# SCH_simple_bracelet_2025-11-06.net
KiCad netlist of a schematic drawn in EasyEDA
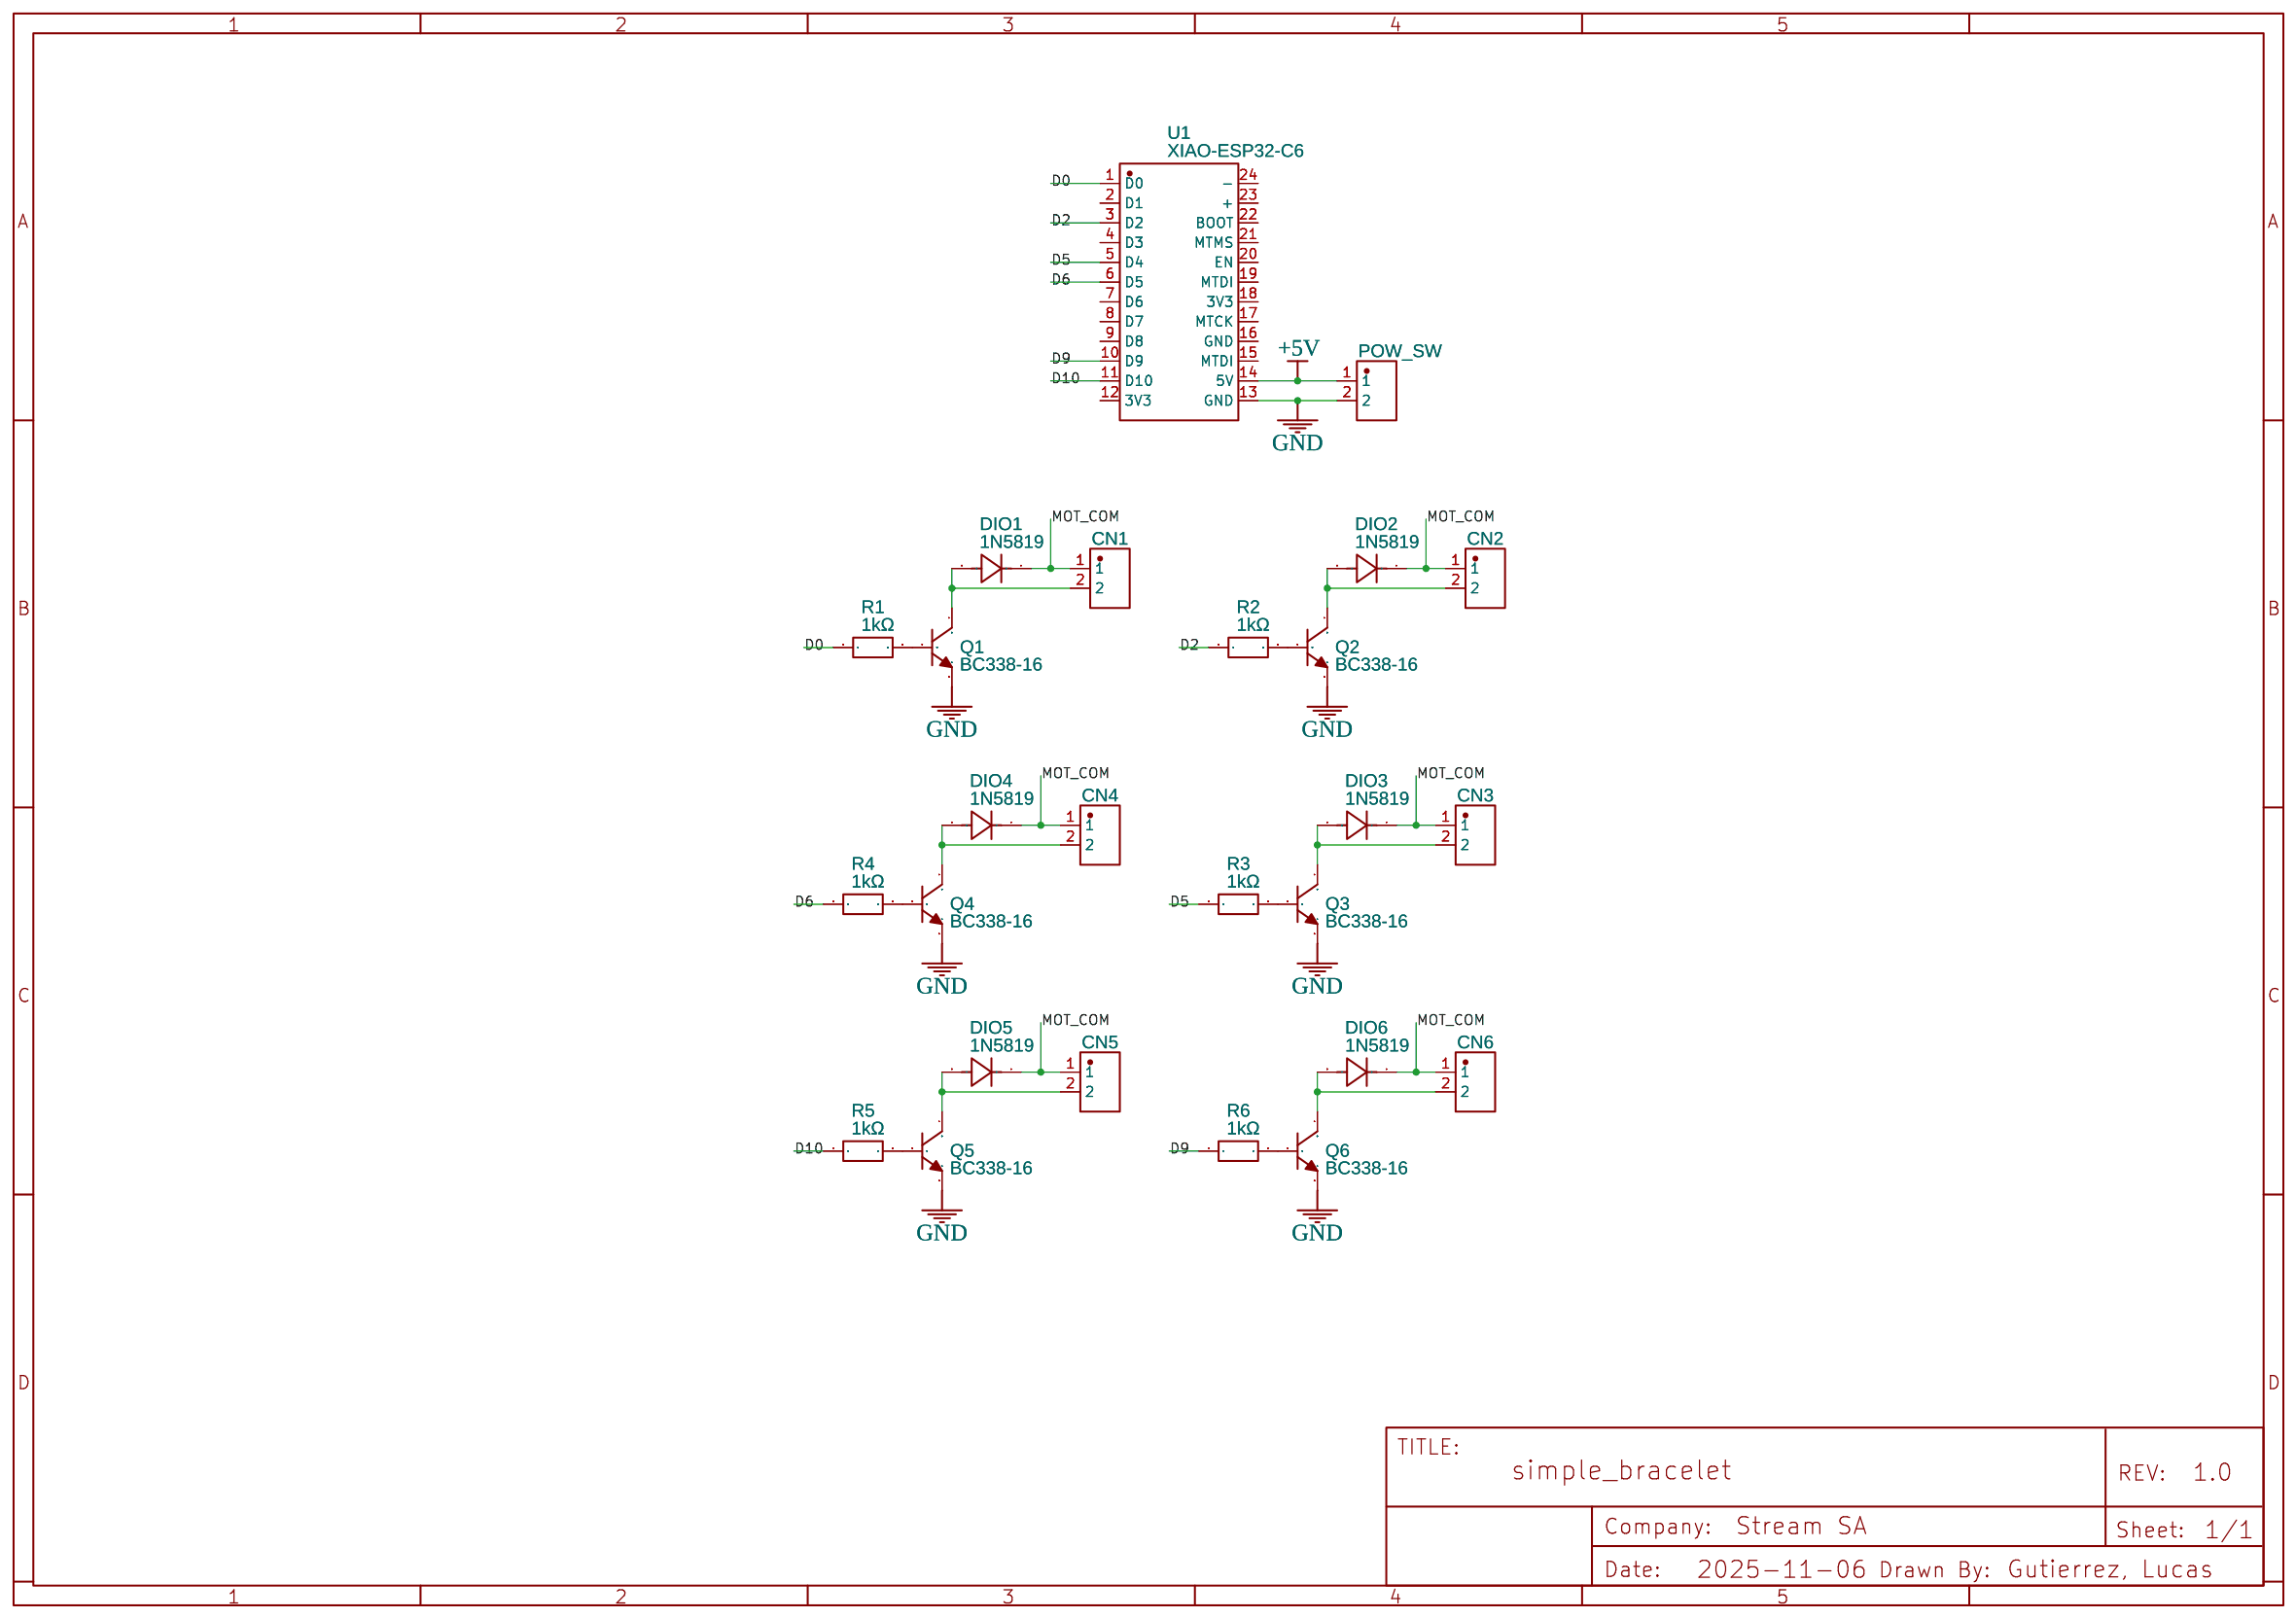
[diagram p0: schematic sheet]

(export (version "E")
  (design (tool "Eeschema 10.0.6"))
  (components
    (comp (ref "CN1")
      (value "2.54-2P WZDK-R PITCH CONNECTOR")
      (fields
        (field (name "Manufacturer Part") "2.54-2P WZDK-R Pitch Connector")
        (field (name "Manufacturer") "SHOU HAN(首韩)")
      )
      (libsource (lib "") (part "2.54-2P WZDK-R PITCH CONNECTOR_1"))
    )
    (comp (ref "CN2")
      (value "2.54-2P WZDK-R PITCH CONNECTOR")
      (fields
        (field (name "Manufacturer Part") "2.54-2P WZDK-R Pitch Connector")
        (field (name "Manufacturer") "SHOU HAN(首韩)")
      )
      (libsource (lib "") (part "2.54-2P WZDK-R PITCH CONNECTOR_1"))
    )
    (comp (ref "CN3")
      (value "2.54-2P WZDK-R PITCH CONNECTOR")
      (fields
        (field (name "Manufacturer Part") "2.54-2P WZDK-R Pitch Connector")
        (field (name "Manufacturer") "SHOU HAN(首韩)")
      )
      (libsource (lib "") (part "2.54-2P WZDK-R PITCH CONNECTOR_1"))
    )
    (comp (ref "CN4")
      (value "2.54-2P WZDK-R PITCH CONNECTOR")
      (fields
        (field (name "Manufacturer Part") "2.54-2P WZDK-R Pitch Connector")
        (field (name "Manufacturer") "SHOU HAN(首韩)")
      )
      (libsource (lib "") (part "2.54-2P WZDK-R PITCH CONNECTOR_1"))
    )
    (comp (ref "CN5")
      (value "2.54-2P WZDK-R PITCH CONNECTOR")
      (fields
        (field (name "Manufacturer Part") "2.54-2P WZDK-R Pitch Connector")
        (field (name "Manufacturer") "SHOU HAN(首韩)")
      )
      (libsource (lib "") (part "2.54-2P WZDK-R PITCH CONNECTOR_1"))
    )
    (comp (ref "CN6")
      (value "2.54-2P WZDK-R PITCH CONNECTOR")
      (fields
        (field (name "Manufacturer Part") "2.54-2P WZDK-R Pitch Connector")
        (field (name "Manufacturer") "SHOU HAN(首韩)")
      )
      (libsource (lib "") (part "2.54-2P WZDK-R PITCH CONNECTOR_1"))
    )
    (comp (ref "DIO1")
      (value "1N5819")
      (fields (field (name "Manufacturer Part") "1N5819散装0658") (field (name "Manufacturer") "YFW(佑风微)"))
      (libsource (lib "") (part "1N5819散装0658"))
    )
    (comp (ref "DIO2")
      (value "1N5819")
      (fields (field (name "Manufacturer Part") "1N5819散装0658") (field (name "Manufacturer") "YFW(佑风微)"))
      (libsource (lib "") (part "1N5819散装0658"))
    )
    (comp (ref "DIO3")
      (value "1N5819")
      (fields (field (name "Manufacturer Part") "1N5819散装0658") (field (name "Manufacturer") "YFW(佑风微)"))
      (libsource (lib "") (part "1N5819散装0658"))
    )
    (comp (ref "DIO4")
      (value "1N5819")
      (fields (field (name "Manufacturer Part") "1N5819散装0658") (field (name "Manufacturer") "YFW(佑风微)"))
      (libsource (lib "") (part "1N5819散装0658"))
    )
    (comp (ref "DIO5")
      (value "1N5819")
      (fields (field (name "Manufacturer Part") "1N5819散装0658") (field (name "Manufacturer") "YFW(佑风微)"))
      (libsource (lib "") (part "1N5819散装0658"))
    )
    (comp (ref "DIO6")
      (value "1N5819")
      (fields (field (name "Manufacturer Part") "1N5819散装0658") (field (name "Manufacturer") "YFW(佑风微)"))
      (libsource (lib "") (part "1N5819散装0658"))
    )
    (comp (ref "POW_SW")
      (value "2.54-2P WZDK-R PITCH CONNECTOR")
      (fields
        (field (name "Manufacturer Part") "2.54-2P WZDK-R Pitch Connector")
        (field (name "Manufacturer") "SHOU HAN(首韩)")
      )
      (libsource (lib "") (part "2.54-2P WZDK-R PITCH CONNECTOR"))
    )
    (comp (ref "Q1")
      (value "BC338-16")
      (fields (field (name "Manufacturer") "LGE(鲁光)"))
      (libsource (lib "") (part "BC338-16"))
    )
    (comp (ref "Q2")
      (value "BC338-16")
      (fields (field (name "Manufacturer") "LGE(鲁光)"))
      (libsource (lib "") (part "BC338-16"))
    )
    (comp (ref "Q3")
      (value "BC338-16")
      (fields (field (name "Manufacturer") "LGE(鲁光)"))
      (libsource (lib "") (part "BC338-16"))
    )
    (comp (ref "Q4")
      (value "BC338-16")
      (fields (field (name "Manufacturer") "LGE(鲁光)"))
      (libsource (lib "") (part "BC338-16"))
    )
    (comp (ref "Q5")
      (value "BC338-16")
      (fields (field (name "Manufacturer") "LGE(鲁光)"))
      (libsource (lib "") (part "BC338-16"))
    )
    (comp (ref "Q6")
      (value "BC338-16")
      (fields (field (name "Manufacturer") "LGE(鲁光)"))
      (libsource (lib "") (part "BC338-16"))
    )
    (comp (ref "R1")
      (value "1kΩ")
      (fields
        (field (name "Manufacturer Part") "CERAMIC RESISTOR 10W/ 2,2 OHM")
        (field (name "Manufacturer") "Visaton")
      )
      (libsource (lib "") (part "CERAMIC RESISTOR 10W/ 2,2 OHM"))
    )
    (comp (ref "R2")
      (value "1kΩ")
      (fields
        (field (name "Manufacturer Part") "CERAMIC RESISTOR 10W/ 2,2 OHM")
        (field (name "Manufacturer") "Visaton")
      )
      (libsource (lib "") (part "CERAMIC RESISTOR 10W/ 2,2 OHM"))
    )
    (comp (ref "R3")
      (value "1kΩ")
      (fields
        (field (name "Manufacturer Part") "CERAMIC RESISTOR 10W/ 2,2 OHM")
        (field (name "Manufacturer") "Visaton")
      )
      (libsource (lib "") (part "CERAMIC RESISTOR 10W/ 2,2 OHM"))
    )
    (comp (ref "R4")
      (value "1kΩ")
      (fields
        (field (name "Manufacturer Part") "CERAMIC RESISTOR 10W/ 2,2 OHM")
        (field (name "Manufacturer") "Visaton")
      )
      (libsource (lib "") (part "CERAMIC RESISTOR 10W/ 2,2 OHM"))
    )
    (comp (ref "R5")
      (value "1kΩ")
      (fields
        (field (name "Manufacturer Part") "CERAMIC RESISTOR 10W/ 2,2 OHM")
        (field (name "Manufacturer") "Visaton")
      )
      (libsource (lib "") (part "CERAMIC RESISTOR 10W/ 2,2 OHM"))
    )
    (comp (ref "R6")
      (value "1kΩ")
      (fields
        (field (name "Manufacturer Part") "CERAMIC RESISTOR 10W/ 2,2 OHM")
        (field (name "Manufacturer") "Visaton")
      )
      (libsource (lib "") (part "CERAMIC RESISTOR 10W/ 2,2 OHM"))
    )
    (comp (ref "U1") (value "XIAO-ESP32-C6") (libsource (lib "") (part "XIAO-ESP32-C6")))
  )
  (nets
    (net (code "1") (name "+5V") (class "Default")
      (node (ref "POW_SW") (pin "1") (pinfunction "1_1") (pintype "unspecified"))
      (node (ref "U1") (pin "14") (pinfunction "5V_14") (pintype "unspecified"))
    )
    (net (code "2") (name "/D0") (class "Default")
      (node (ref "R1") (pin "1") (pinfunction "1_1") (pintype "unspecified"))
      (node (ref "U1") (pin "1") (pinfunction "D0_1") (pintype "unspecified"))
    )
    (net (code "3") (name "/D2") (class "Default")
      (node (ref "R2") (pin "1") (pinfunction "1_1") (pintype "unspecified"))
      (node (ref "U1") (pin "3") (pinfunction "D2_3") (pintype "unspecified"))
    )
    (net (code "4") (name "/D5") (class "Default")
      (node (ref "R3") (pin "1") (pinfunction "1_1") (pintype "unspecified"))
      (node (ref "U1") (pin "5") (pinfunction "D4_5") (pintype "unspecified"))
    )
    (net (code "5") (name "/D6") (class "Default")
      (node (ref "R4") (pin "1") (pinfunction "1_1") (pintype "unspecified"))
      (node (ref "U1") (pin "6") (pinfunction "D5_6") (pintype "unspecified"))
    )
    (net (code "6") (name "/D9") (class "Default")
      (node (ref "R6") (pin "1") (pinfunction "1_1") (pintype "unspecified"))
      (node (ref "U1") (pin "10") (pinfunction "D9_10") (pintype "unspecified"))
    )
    (net (code "7") (name "/D10") (class "Default")
      (node (ref "R5") (pin "1") (pinfunction "1_1") (pintype "unspecified"))
      (node (ref "U1") (pin "11") (pinfunction "D10_11") (pintype "unspecified"))
    )
    (net (code "8") (name "/MOT_COM") (class "Default")
      (node (ref "CN1") (pin "1") (pinfunction "1_1") (pintype "unspecified"))
      (node (ref "CN2") (pin "1") (pinfunction "1_1") (pintype "unspecified"))
      (node (ref "CN3") (pin "1") (pinfunction "1_1") (pintype "unspecified"))
      (node (ref "CN4") (pin "1") (pinfunction "1_1") (pintype "unspecified"))
      (node (ref "CN5") (pin "1") (pinfunction "1_1") (pintype "unspecified"))
      (node (ref "CN6") (pin "1") (pinfunction "1_1") (pintype "unspecified"))
      (node (ref "DIO1") (pin "1") (pinfunction "K_1") (pintype "unspecified"))
      (node (ref "DIO2") (pin "1") (pinfunction "K_1") (pintype "unspecified"))
      (node (ref "DIO3") (pin "1") (pinfunction "K_1") (pintype "unspecified"))
      (node (ref "DIO4") (pin "1") (pinfunction "K_1") (pintype "unspecified"))
      (node (ref "DIO5") (pin "1") (pinfunction "K_1") (pintype "unspecified"))
      (node (ref "DIO6") (pin "1") (pinfunction "K_1") (pintype "unspecified"))
    )
    (net (code "9") (name "GND") (class "Default")
      (node (ref "POW_SW") (pin "2") (pinfunction "2_2") (pintype "unspecified"))
      (node (ref "Q1") (pin "3") (pinfunction "E_3") (pintype "input"))
      (node (ref "Q2") (pin "3") (pinfunction "E_3") (pintype "input"))
      (node (ref "Q3") (pin "3") (pinfunction "E_3") (pintype "input"))
      (node (ref "Q4") (pin "3") (pinfunction "E_3") (pintype "input"))
      (node (ref "Q5") (pin "3") (pinfunction "E_3") (pintype "input"))
      (node (ref "Q6") (pin "3") (pinfunction "E_3") (pintype "input"))
      (node (ref "U1") (pin "13") (pinfunction "GND_13") (pintype "unspecified"))
    )
    (net (code "10") (name "Net-(DIO1-A)") (class "Default")
      (node (ref "CN1") (pin "2") (pinfunction "2_2") (pintype "unspecified"))
      (node (ref "DIO1") (pin "2") (pinfunction "A_2") (pintype "unspecified"))
      (node (ref "Q1") (pin "1") (pinfunction "C_1") (pintype "input"))
    )
    (net (code "11") (name "Net-(DIO2-A)") (class "Default")
      (node (ref "CN2") (pin "2") (pinfunction "2_2") (pintype "unspecified"))
      (node (ref "DIO2") (pin "2") (pinfunction "A_2") (pintype "unspecified"))
      (node (ref "Q2") (pin "1") (pinfunction "C_1") (pintype "input"))
    )
    (net (code "12") (name "Net-(DIO3-A)") (class "Default")
      (node (ref "CN3") (pin "2") (pinfunction "2_2") (pintype "unspecified"))
      (node (ref "DIO3") (pin "2") (pinfunction "A_2") (pintype "unspecified"))
      (node (ref "Q3") (pin "1") (pinfunction "C_1") (pintype "input"))
    )
    (net (code "13") (name "Net-(DIO4-A)") (class "Default")
      (node (ref "CN4") (pin "2") (pinfunction "2_2") (pintype "unspecified"))
      (node (ref "DIO4") (pin "2") (pinfunction "A_2") (pintype "unspecified"))
      (node (ref "Q4") (pin "1") (pinfunction "C_1") (pintype "input"))
    )
    (net (code "14") (name "Net-(DIO5-A)") (class "Default")
      (node (ref "CN5") (pin "2") (pinfunction "2_2") (pintype "unspecified"))
      (node (ref "DIO5") (pin "2") (pinfunction "A_2") (pintype "unspecified"))
      (node (ref "Q5") (pin "1") (pinfunction "C_1") (pintype "input"))
    )
    (net (code "15") (name "Net-(DIO6-A)") (class "Default")
      (node (ref "CN6") (pin "2") (pinfunction "2_2") (pintype "unspecified"))
      (node (ref "DIO6") (pin "2") (pinfunction "A_2") (pintype "unspecified"))
      (node (ref "Q6") (pin "1") (pinfunction "C_1") (pintype "input"))
    )
    (net (code "16") (name "Net-(Q1-B)") (class "Default")
      (node (ref "Q1") (pin "2") (pinfunction "B_2") (pintype "input"))
      (node (ref "R1") (pin "2") (pinfunction "2_2") (pintype "unspecified"))
    )
    (net (code "17") (name "Net-(Q2-B)") (class "Default")
      (node (ref "Q2") (pin "2") (pinfunction "B_2") (pintype "input"))
      (node (ref "R2") (pin "2") (pinfunction "2_2") (pintype "unspecified"))
    )
    (net (code "18") (name "Net-(Q3-B)") (class "Default")
      (node (ref "Q3") (pin "2") (pinfunction "B_2") (pintype "input"))
      (node (ref "R3") (pin "2") (pinfunction "2_2") (pintype "unspecified"))
    )
    (net (code "19") (name "Net-(Q4-B)") (class "Default")
      (node (ref "Q4") (pin "2") (pinfunction "B_2") (pintype "input"))
      (node (ref "R4") (pin "2") (pinfunction "2_2") (pintype "unspecified"))
    )
    (net (code "20") (name "Net-(Q5-B)") (class "Default")
      (node (ref "Q5") (pin "2") (pinfunction "B_2") (pintype "input"))
      (node (ref "R5") (pin "2") (pinfunction "2_2") (pintype "unspecified"))
    )
    (net (code "21") (name "Net-(Q6-B)") (class "Default")
      (node (ref "Q6") (pin "2") (pinfunction "B_2") (pintype "input"))
      (node (ref "R6") (pin "2") (pinfunction "2_2") (pintype "unspecified"))
    )
    (net (code "22") (name "unconnected-(U1-+-Pad23)") (class "Default")
      (node (ref "U1") (pin "23") (pinfunction "+_23") (pintype "unspecified"))
    )
    (net (code "23") (name "unconnected-(U1---Pad24)") (class "Default")
      (node (ref "U1") (pin "24") (pinfunction "-_24") (pintype "unspecified"))
    )
    (net (code "24") (name "unconnected-(U1-3V3-Pad12)") (class "Default")
      (node (ref "U1") (pin "12") (pinfunction "3V3_12") (pintype "unspecified"))
    )
    (net (code "25") (name "unconnected-(U1-3V3-Pad18)") (class "Default")
      (node (ref "U1") (pin "18") (pinfunction "3V3_18") (pintype "unspecified"))
    )
    (net (code "26") (name "unconnected-(U1-BOOT-Pad22)") (class "Default")
      (node (ref "U1") (pin "22") (pinfunction "BOOT_22") (pintype "unspecified"))
    )
    (net (code "27") (name "unconnected-(U1-D1-Pad2)") (class "Default")
      (node (ref "U1") (pin "2") (pinfunction "D1_2") (pintype "unspecified"))
    )
    (net (code "28") (name "unconnected-(U1-D3-Pad4)") (class "Default")
      (node (ref "U1") (pin "4") (pinfunction "D3_4") (pintype "unspecified"))
    )
    (net (code "29") (name "unconnected-(U1-D6-Pad7)") (class "Default")
      (node (ref "U1") (pin "7") (pinfunction "D6_7") (pintype "unspecified"))
    )
    (net (code "30") (name "unconnected-(U1-D7-Pad8)") (class "Default")
      (node (ref "U1") (pin "8") (pinfunction "D7_8") (pintype "unspecified"))
    )
    (net (code "31") (name "unconnected-(U1-D8-Pad9)") (class "Default")
      (node (ref "U1") (pin "9") (pinfunction "D8_9") (pintype "unspecified"))
    )
    (net (code "32") (name "unconnected-(U1-EN-Pad20)") (class "Default")
      (node (ref "U1") (pin "20") (pinfunction "EN_20") (pintype "unspecified"))
    )
    (net (code "33") (name "unconnected-(U1-GND-Pad16)") (class "Default")
      (node (ref "U1") (pin "16") (pinfunction "GND_16") (pintype "unspecified"))
    )
    (net (code "34") (name "unconnected-(U1-MTCK-Pad17)") (class "Default")
      (node (ref "U1") (pin "17") (pinfunction "MTCK_17") (pintype "unspecified"))
    )
    (net (code "35") (name "unconnected-(U1-MTDI-Pad15)") (class "Default")
      (node (ref "U1") (pin "15") (pinfunction "MTDI_15") (pintype "unspecified"))
    )
    (net (code "36") (name "unconnected-(U1-MTDI-Pad19)") (class "Default")
      (node (ref "U1") (pin "19") (pinfunction "MTDI_19") (pintype "unspecified"))
    )
    (net (code "37") (name "unconnected-(U1-MTMS-Pad21)") (class "Default")
      (node (ref "U1") (pin "21") (pinfunction "MTMS_21") (pintype "unspecified"))
    )
  )
)
